# attiny85.net
KiCad netlist of a schematic drawn in EAGLE
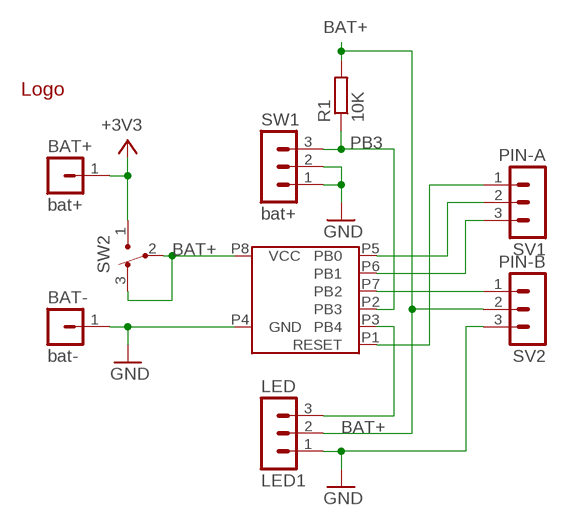
[diagram p0: schematic, sheet 1]

(export (version "E")
  (design (tool "Eeschema 10.0.6"))
  (components
    (comp (ref "ATTINY85-1")
      (value "ATTINY85")
      (footprint "eagle-import:ATTINY85-20SUR")
      (libsource (lib "eagle-import") (part "ATTINY85SOP8"))
    )
    (comp (ref "BAT+")
      (value "bat+")
      (footprint "eagle-import:PINHEAD-MA01-1")
      (libsource (lib "eagle-import") (part "PINHEAD-MA01-1"))
    )
    (comp (ref "BAT-")
      (value "bat-")
      (footprint "eagle-import:PINHEAD-MA01-1")
      (libsource (lib "eagle-import") (part "PINHEAD-MA01-1"))
    )
    (comp (ref "LED")
      (value "LED1")
      (footprint "eagle-import:PINHEAD-MA03-1")
      (libsource (lib "eagle-import") (part "ytani1_30941153_PINHEAD-MA03-1"))
    )
    (comp (ref "LOGO1")
      (value "LOGO-YT")
      (footprint "eagle-import:LOGO-YT1")
      (libsource (lib "eagle-import") (part "LOGO-YT"))
    )
    (comp (ref "R1")
      (value "10K")
      (footprint "eagle-import:M3216")
      (libsource (lib "eagle-import") (part "R-EU_M3216"))
    )
    (comp (ref "SV1")
      (value "PIN-A")
      (footprint "eagle-import:PINHEAD-MA03-1")
      (libsource (lib "eagle-import") (part "PINHEAD-MA03-1"))
    )
    (comp (ref "SV2")
      (value "PIN-B")
      (footprint "eagle-import:PINHEAD-MA03-1")
      (libsource (lib "eagle-import") (part "PINHEAD-MA03-1"))
    )
    (comp (ref "SW1")
      (value "bat+")
      (footprint "eagle-import:PINHEAD-MA03-1")
      (libsource (lib "eagle-import") (part "PINHEAD-MA03-1"))
    )
    (comp (ref "SW2")
      (value "POWER")
      (footprint "eagle-import:SW3-1")
      (fields (field (name "MF") "HiLetgo"))
      (libsource (lib "eagle-import") (part "SW3-1"))
    )
  )
  (nets
    (net (code "1") (name "+3V3") (class "Default")
      (node (ref "BAT+") (pin "1") (pinfunction "1_1") (pintype "passive"))
      (node (ref "SW2") (pin "1") (pinfunction "1_1") (pintype "passive"))
    )
    (net (code "2") (name "/BAT+") (class "Default")
      (node (ref "ATTINY85-1") (pin "P8") (pinfunction "VCC_P8") (pintype "bidirectional"))
      (node (ref "LED") (pin "2") (pinfunction "2_2") (pintype "passive"))
      (node (ref "R1") (pin "2") (pinfunction "2_2") (pintype "passive"))
      (node (ref "SV2") (pin "2") (pinfunction "2_2") (pintype "passive"))
      (node (ref "SW2") (pin "2") (pinfunction "2_2") (pintype "passive"))
      (node (ref "SW2") (pin "3") (pinfunction "3_3") (pintype "passive"))
    )
    (net (code "3") (name "/PB3") (class "Default")
      (node (ref "ATTINY85-1") (pin "P2") (pinfunction "PB3_P2") (pintype "bidirectional"))
      (node (ref "R1") (pin "1") (pinfunction "1_1") (pintype "passive"))
      (node (ref "SW1") (pin "3") (pinfunction "3_3") (pintype "passive"))
    )
    (net (code "4") (name "GND") (class "Default")
      (node (ref "ATTINY85-1") (pin "P4") (pinfunction "GND_P4") (pintype "bidirectional"))
      (node (ref "BAT-") (pin "1") (pinfunction "1_1") (pintype "passive"))
      (node (ref "LED") (pin "1") (pinfunction "1_1") (pintype "passive"))
      (node (ref "SV2") (pin "3") (pinfunction "3_3") (pintype "passive"))
      (node (ref "SW1") (pin "1") (pinfunction "1_1") (pintype "passive"))
      (node (ref "SW1") (pin "2") (pinfunction "2_2") (pintype "passive"))
    )
    (net (code "5") (name "Net-(ATTINY85-1-PB0)") (class "Default")
      (node (ref "ATTINY85-1") (pin "P5") (pinfunction "PB0_P5") (pintype "bidirectional"))
      (node (ref "SV1") (pin "2") (pinfunction "2_2") (pintype "passive"))
    )
    (net (code "6") (name "Net-(ATTINY85-1-PB1)") (class "Default")
      (node (ref "ATTINY85-1") (pin "P6") (pinfunction "PB1_P6") (pintype "bidirectional"))
      (node (ref "SV1") (pin "3") (pinfunction "3_3") (pintype "passive"))
    )
    (net (code "7") (name "Net-(ATTINY85-1-PB2)") (class "Default")
      (node (ref "ATTINY85-1") (pin "P7") (pinfunction "PB2_P7") (pintype "bidirectional"))
      (node (ref "SV2") (pin "1") (pinfunction "1_1") (pintype "passive"))
    )
    (net (code "8") (name "Net-(ATTINY85-1-PB4)") (class "Default")
      (node (ref "ATTINY85-1") (pin "P3") (pinfunction "PB4_P3") (pintype "bidirectional"))
      (node (ref "LED") (pin "3") (pinfunction "3_3") (pintype "passive"))
    )
    (net (code "9") (name "Net-(ATTINY85-1-RESET)") (class "Default")
      (node (ref "ATTINY85-1") (pin "P1") (pinfunction "RESET_P1") (pintype "bidirectional"))
      (node (ref "SV1") (pin "1") (pinfunction "1_1") (pintype "passive"))
    )
  )
)
